# BLDC_Motor_Reverser.net
KiCad netlist of a schematic drawn in Altium Designer
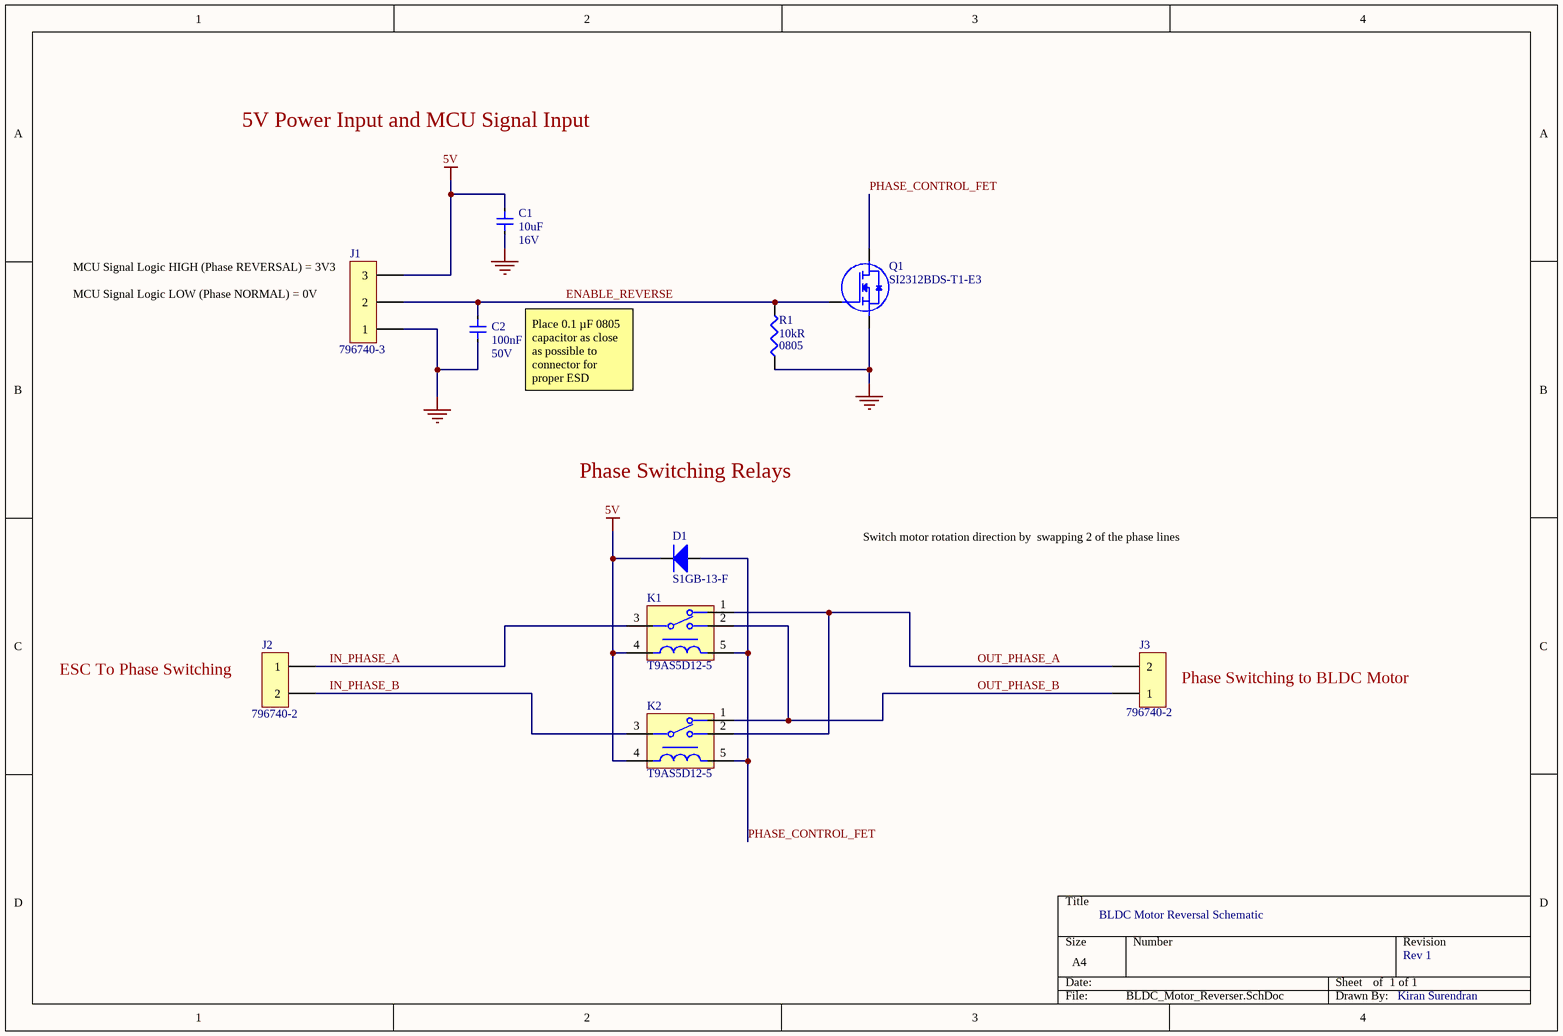
[diagram p0: BLDC_Motor_Reverser.SchDoc]

(export (version "E")
  (design (tool "Eeschema 10.0.6"))
  (components
    (comp (ref "C1")
      (value "C0805C106K4PACTU")
      (footprint "C0805C106K4PACTU")
      (description "CERAMIC CAPACITOR, 10UF, 16V, X5R, 10%, 0805")
      (fields (field (name "VOLTAGE RATING") "16V") (field (name "CAPACITANCE") "10uF"))
      (libsource (lib "BLDC_Motor_Lib") (part "C0805C106K4PACTU"))
    )
    (comp (ref "C2")
      (value "C0805C104K5RACTU")
      (footprint "C0805C104K5RACTU")
      (description "Cap Ceramic 0.1uF 50V X7R 10% SMD 2.0 x 1.2 mm 125 C Paper T/R")
      (fields (field (name "VOLTAGE RATING") "50V") (field (name "CAPACITANCE") "100nF"))
      (libsource (lib "BLDC_Motor_Lib") (part "C0805C104K5RACTU"))
    )
    (comp (ref "D1")
      (value "S1GB-13-F")
      (footprint "S1GB-13-F")
      (description "Flyback Diode for SPDT")
      (libsource (lib "BLDC_Motor_Lib") (part "S1GB-13-F"))
    )
    (comp (ref "J1")
      (value "796740-3")
      (footprint "796740-3")
      (description "TERM BLK 3P SIDE ENT 6.35MM PCB")
      (libsource (lib "BLDC_Motor_Lib") (part "796740-3"))
    )
    (comp (ref "J2")
      (value "796740-2")
      (footprint "796740-2")
      (description "TERMINAL BLOCK, PLUG, 2POS, 24-10AWG")
      (fields (field (name "MANUFACTURER") "TE Connectivity"))
      (libsource (lib "") (part "796740-2_1"))
    )
    (comp (ref "J3")
      (value "796740-2")
      (footprint "796740-2")
      (description "TERMINAL BLOCK, PLUG, 2POS, 24-10AWG")
      (fields (field (name "MANUFACTURER") "TE Connectivity"))
      (libsource (lib "BLDC_Motor_Lib") (part "796740-2"))
    )
    (comp (ref "K1")
      (value "T9AS5D12-5")
      (footprint "T9AS5D12-5")
      (description "RELAY GEN PURPOSE SPDT 20A 5V")
      (libsource (lib "BLDC_Motor_Lib") (part "T9AS5D12-5"))
    )
    (comp (ref "K2")
      (value "T9AS5D12-5")
      (footprint "T9AS5D12-5")
      (description "RELAY GEN PURPOSE SPDT 20A 5V")
      (libsource (lib "BLDC_Motor_Lib") (part "T9AS5D12-5"))
    )
    (comp (ref "Q1")
      (value "SI2312BDS-T1-E3")
      (footprint "SI2312BDS-T1-E3")
      (description "MOSFET")
      (libsource (lib "BLDC_Motor_Lib") (part "SI2312BDS-T1-E3"))
    )
    (comp (ref "R1")
      (value "RC0805JR-0710KL")
      (footprint "RC0805JR-0710KL")
      (description "Res Thick Film 0805 10K Ohm 5% 1/8W ±100ppm/°C Molded SMD Paper T/R")
      (fields
        (field (name "TOLERANCE") "5%")
        (field (name "PACKAGE") "0805")
        (field (name "RESISTANCE") "10kR")
      )
      (libsource (lib "BLDC_Motor_Lib") (part "RC0805JR-0710KL"))
    )
  )
  (nets
    (net (code "1") (name "/ENABLE_REVERSE") (class "Default")
      (node (ref "C2") (pin "2") (pintype "passive"))
      (node (ref "J1") (pin "2") (pinfunction "2_2") (pintype "passive"))
      (node (ref "Q1") (pin "1") (pinfunction "Gate_1") (pintype "passive"))
      (node (ref "R1") (pin "2") (pintype "passive"))
    )
    (net (code "2") (name "/IN_PHASE_A") (class "Default")
      (node (ref "J2") (pin "1") (pinfunction "1_1") (pintype "passive"))
      (node (ref "K1") (pin "3") (pinfunction "COM_3") (pintype "passive"))
    )
    (net (code "3") (name "/IN_PHASE_B") (class "Default")
      (node (ref "J2") (pin "2") (pinfunction "2_2") (pintype "passive"))
      (node (ref "K2") (pin "3") (pinfunction "COM_3") (pintype "passive"))
    )
    (net (code "4") (name "/OUT_PHASE_A") (class "Default")
      (node (ref "J3") (pin "2") (pinfunction "2_2") (pintype "passive"))
      (node (ref "K1") (pin "1") (pinfunction "NC_1") (pintype "passive"))
      (node (ref "K2") (pin "2") (pinfunction "NO_2") (pintype "passive"))
    )
    (net (code "5") (name "/OUT_PHASE_B") (class "Default")
      (node (ref "J3") (pin "1") (pinfunction "1_1") (pintype "passive"))
      (node (ref "K1") (pin "2") (pinfunction "NO_2") (pintype "passive"))
      (node (ref "K2") (pin "1") (pinfunction "NC_1") (pintype "passive"))
    )
    (net (code "6") (name "/PHASE_CONTROL_FET") (class "Default")
      (node (ref "D1") (pin "1") (pinfunction "+_1") (pintype "passive"))
      (node (ref "K1") (pin "5") (pinfunction "5_5") (pintype "passive"))
      (node (ref "K2") (pin "5") (pinfunction "5_5") (pintype "passive"))
      (node (ref "Q1") (pin "3") (pinfunction "Drain_3") (pintype "passive"))
    )
    (net (code "7") (name "5V") (class "Default")
      (node (ref "C1") (pin "2") (pintype "passive"))
      (node (ref "D1") (pin "2") (pinfunction "-_2") (pintype "passive"))
      (node (ref "J1") (pin "3") (pinfunction "3_3") (pintype "passive"))
      (node (ref "K1") (pin "4") (pinfunction "4_4") (pintype "passive"))
      (node (ref "K2") (pin "4") (pinfunction "4_4") (pintype "passive"))
    )
    (net (code "8") (name "GND") (class "Default")
      (node (ref "C1") (pin "1") (pintype "passive"))
      (node (ref "C2") (pin "1") (pintype "passive"))
      (node (ref "J1") (pin "1") (pinfunction "1_1") (pintype "passive"))
      (node (ref "Q1") (pin "2") (pinfunction "Source_2") (pintype "passive"))
      (node (ref "R1") (pin "1") (pintype "passive"))
    )
  )
)
